# Current_DC.net
KiCad netlist of a schematic drawn in Altium Designer
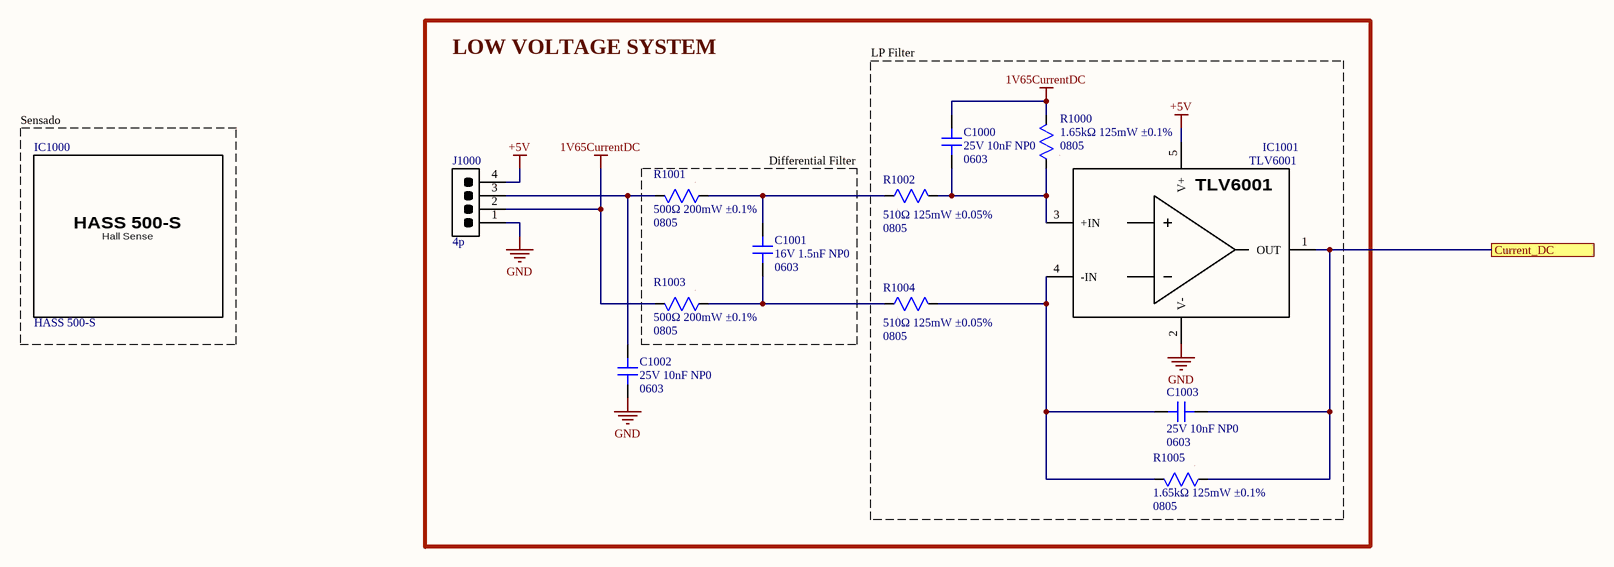
[diagram p0: Current_DC.SchDoc]

(export (version "E")
  (design (tool "Eeschema 10.0.6"))
  (components
    (comp (ref "C1000")
      (value "25V 10nF NP0")
      (footprint "CAP SMD 0603")
      (description "Condensadores de cerámica multicapa (MLCC- SMD/SMT) 0.01 uF 25 VDC 1% 0603 C0G (NP0) AEC-Q200")
      (fields
        (field (name "PACKAGE") "0603")
        (field (name "MPN") "GRT1885C1E103FA02D")
        (field (name "MANUFACTURER") "muRata")
      )
      (libsource (lib "eUSR_Database") (part "CAP non polarized"))
    )
    (comp (ref "C1001")
      (value "16V 1.5nF NP0")
      (footprint "CAP SMD 0603")
      (description "Condensadores de cerámica multicapa (MLCC- SMD/SMT) 25V 1500pF C0G 0603 1%")
      (fields
        (field (name "PACKAGE") "0603")
        (field (name "MPN") "C0603C152F3GECTU")
        (field (name "MANUFACTURER") "KEMET")
      )
      (libsource (lib "eUSR_Database") (part "CAP non polarized"))
    )
    (comp (ref "C1002")
      (value "25V 10nF NP0")
      (footprint "CAP SMD 0603")
      (description "Condensadores de cerámica multicapa (MLCC- SMD/SMT) 0.01 uF 25 VDC 1% 0603 C0G (NP0) AEC-Q200")
      (fields
        (field (name "PACKAGE") "0603")
        (field (name "MPN") "GRT1885C1E103FA02D")
        (field (name "MANUFACTURER") "muRata")
      )
      (libsource (lib "eUSR_Database") (part "CAP non polarized"))
    )
    (comp (ref "C1003")
      (value "25V 10nF NP0")
      (footprint "CAP SMD 0603")
      (description "Condensadores de cerámica multicapa (MLCC- SMD/SMT) 0.01 uF 25 VDC 1% 0603 C0G (NP0) AEC-Q200")
      (fields
        (field (name "PACKAGE") "0603")
        (field (name "MPN") "GRT1885C1E103FA02D")
        (field (name "MANUFACTURER") "muRata")
      )
      (libsource (lib "eUSR_Database") (part "CAP non polarized"))
    )
    (comp (ref "IC1000")
      (value "HASS 500-S")
      (footprint "HASS 500-S")
      (description "Sensores de corriente montados en placa")
      (fields (field (name "MANUFACTURER") "LEM"))
      (libsource (lib "eUSR_Database") (part "HASS 500-S"))
    )
    (comp (ref "IC1001")
      (value "TLV6001")
      (footprint "SOT-23-5")
      (fields (field (name "MPN") "TLV6001UIDBVR") (field (name "MANUFACTURER") "Texas Instruments"))
      (libsource (lib "eUSR_Database") (part "TLV6001"))
    )
    (comp (ref "J1000")
      (value "4p")
      (footprint "B4B-XH-A-BK(LF)(SN)")
      (description "Alojamientos de cables y cabecera XH HEADER (TOP)")
      (fields (field (name "MPN") "B4B-XH-A-BK(LF)(SN)") (field (name "MANUFACTURER") "JST"))
      (libsource (lib "eUSR_Database") (part "CONN 4P"))
    )
    (comp (ref "R1000")
      (value "1.65kΩ 125mW ±0.1%")
      (footprint "RES SMD 0805")
      (description "Thin Film Resistors MCU 0805-15 0.1% P1 1K65")
      (fields
        (field (name "PACKAGE") "0805")
        (field (name "MPN") "MCU08050E1651BP100")
        (field (name "MANUFACTURER") "Vishay")
      )
      (libsource (lib "eUSR_Database") (part "RES"))
    )
    (comp (ref "R1001")
      (value "500Ω 200mW ±0.1%")
      (footprint "RES SMD 0805")
      (description "Resistores de película fina - SMD 0.2W 500ohm 0.1% 10ppm")
      (fields
        (field (name "PACKAGE") "0805")
        (field (name "MPN") "PTN0805Y5000BST1")
        (field (name "MANUFACTURER") "Vishay")
      )
      (libsource (lib "eUSR_Database") (part "RES"))
    )
    (comp (ref "R1002")
      (value "510Ω 125mW ±0.05%")
      (footprint "RES SMD 0805")
      (description "Resistores de película fina - SMD 1/8W 510 Ohms 0.05% 0805 10ppm")
      (fields
        (field (name "PACKAGE") "0805")
        (field (name "MPN") "RG2012N-511-W-T1")
        (field (name "MANUFACTURER") "Susumu")
      )
      (libsource (lib "eUSR_Database") (part "RES"))
    )
    (comp (ref "R1003")
      (value "500Ω 200mW ±0.1%")
      (footprint "RES SMD 0805")
      (description "Resistores de película fina - SMD 0.2W 500ohm 0.1% 10ppm")
      (fields
        (field (name "PACKAGE") "0805")
        (field (name "MPN") "PTN0805Y5000BST1")
        (field (name "MANUFACTURER") "Vishay")
      )
      (libsource (lib "eUSR_Database") (part "RES"))
    )
    (comp (ref "R1004")
      (value "510Ω 125mW ±0.05%")
      (footprint "RES SMD 0805")
      (description "Resistores de película fina - SMD 1/8W 510 Ohms 0.05% 0805 10ppm")
      (fields
        (field (name "PACKAGE") "0805")
        (field (name "MPN") "RG2012N-511-W-T1")
        (field (name "MANUFACTURER") "Susumu")
      )
      (libsource (lib "eUSR_Database") (part "RES"))
    )
    (comp (ref "R1005")
      (value "1.65kΩ 125mW ±0.1%")
      (footprint "RES SMD 0805")
      (description "Thin Film Resistors MCU 0805-15 0.1% P1 1K65")
      (fields
        (field (name "PACKAGE") "0805")
        (field (name "MPN") "MCU08050E1651BP100")
        (field (name "MANUFACTURER") "Vishay")
      )
      (libsource (lib "eUSR_Database") (part "RES"))
    )
  )
  (nets
    (net (code "1") (name "+5V") (class "Default")
      (node (ref "IC1001") (pin "5") (pinfunction "V+_5") (pintype "passive"))
      (node (ref "J1000") (pin "4") (pinfunction "4_4") (pintype "passive"))
    )
    (net (code "2") (name "/Current_DC") (class "Default")
      (node (ref "C1003") (pin "2") (pinfunction "2_2") (pintype "passive"))
      (node (ref "IC1001") (pin "1") (pinfunction "OUT_1") (pintype "passive"))
      (node (ref "R1005") (pin "1") (pinfunction "1_1") (pintype "passive"))
    )
    (net (code "3") (name "1V65CurrentDC") (class "Default")
      (node (ref "C1000") (pin "1") (pinfunction "1_1") (pintype "passive"))
      (node (ref "J1000") (pin "2") (pinfunction "2_2") (pintype "passive"))
      (node (ref "R1000") (pin "2") (pinfunction "2_2") (pintype "passive"))
      (node (ref "R1003") (pin "2") (pinfunction "2_2") (pintype "passive"))
    )
    (net (code "4") (name "GND") (class "Default")
      (node (ref "C1002") (pin "2") (pinfunction "2_2") (pintype "passive"))
      (node (ref "IC1001") (pin "2") (pinfunction "V-_2") (pintype "passive"))
      (node (ref "J1000") (pin "1") (pinfunction "1_1") (pintype "passive"))
    )
    (net (code "5") (name "Net-(C1001-Pad1)") (class "Default")
      (node (ref "C1001") (pin "1") (pinfunction "1_1") (pintype "passive"))
      (node (ref "R1001") (pin "1") (pinfunction "1_1") (pintype "passive"))
      (node (ref "R1002") (pin "1") (pinfunction "1_1") (pintype "passive"))
    )
    (net (code "6") (name "Net-(C1001-Pad2)") (class "Default")
      (node (ref "C1001") (pin "2") (pinfunction "2_2") (pintype "passive"))
      (node (ref "R1003") (pin "1") (pinfunction "1_1") (pintype "passive"))
      (node (ref "R1004") (pin "1") (pinfunction "1_1") (pintype "passive"))
    )
    (net (code "7") (name "Net-(C1002-Pad1)") (class "Default")
      (node (ref "C1002") (pin "1") (pinfunction "1_1") (pintype "passive"))
      (node (ref "J1000") (pin "3") (pinfunction "3_3") (pintype "passive"))
      (node (ref "R1001") (pin "2") (pinfunction "2_2") (pintype "passive"))
    )
    (net (code "8") (name "Net-(IC1001-+IN)") (class "Default")
      (node (ref "C1000") (pin "2") (pinfunction "2_2") (pintype "passive"))
      (node (ref "IC1001") (pin "3") (pinfunction "+IN_3") (pintype "passive"))
      (node (ref "R1000") (pin "1") (pinfunction "1_1") (pintype "passive"))
      (node (ref "R1002") (pin "2") (pinfunction "2_2") (pintype "passive"))
    )
    (net (code "9") (name "Net-(IC1001--IN)") (class "Default")
      (node (ref "C1003") (pin "1") (pinfunction "1_1") (pintype "passive"))
      (node (ref "IC1001") (pin "4") (pinfunction "-IN_4") (pintype "passive"))
      (node (ref "R1004") (pin "2") (pinfunction "2_2") (pintype "passive"))
      (node (ref "R1005") (pin "2") (pinfunction "2_2") (pintype "passive"))
    )
  )
)
